# power_supplies.net
KiCad netlist of a schematic drawn in Altium Designer
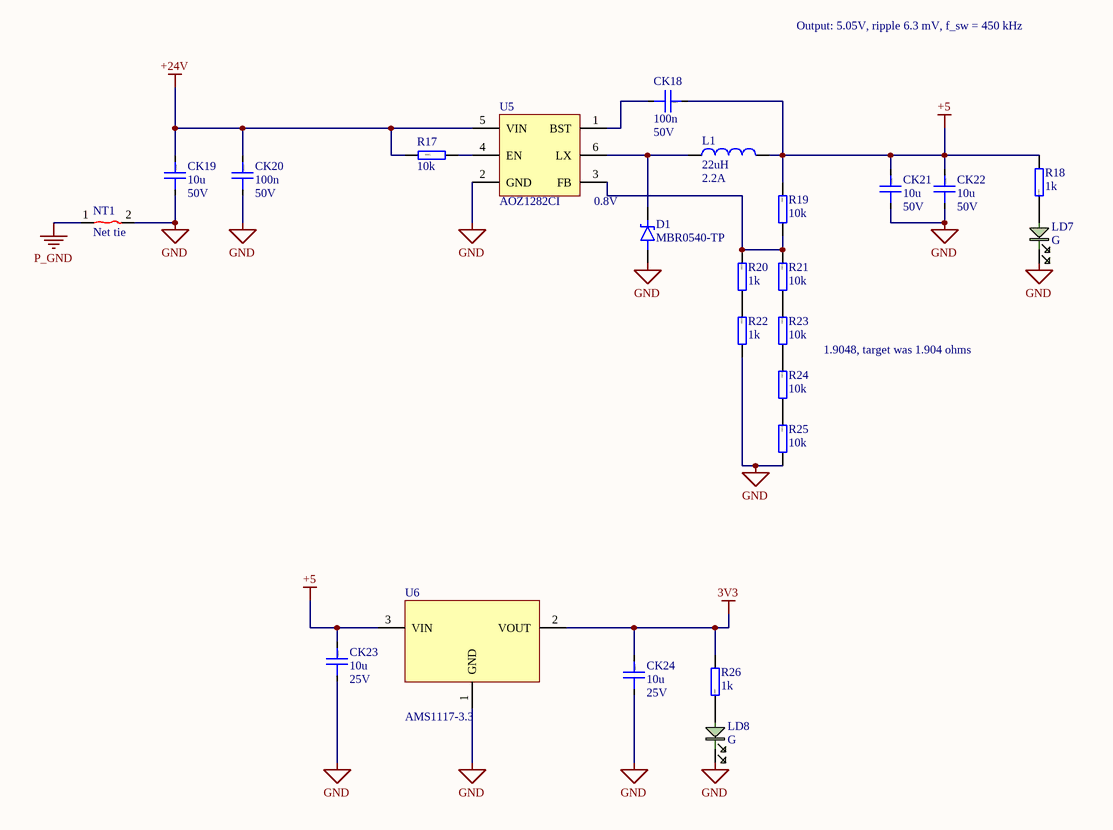
[diagram p0: power_supplies.SchDoc]

(export (version "E")
  (design (tool "Eeschema 10.0.6"))
  (components
    (comp (ref "CK18")
      (value "100n")
      (footprint "CAP0603")
      (description "50V 100nF X7R ±10% 0603 Multilayer Ceramic Capacitors MLCC - SMD/SMT ROHS")
      (fields (field (name "JLCPCB PART") "C14663") (field (name "VOLTAGE RATING") "50V"))
      (libsource (lib "Kubikova ultra knihovna") (part "Cap 100n 50V 0603"))
    )
    (comp (ref "CK19")
      (value "10u")
      (footprint "CAP1206")
      (description "50V 10uF X5R ±10% 1206 Multilayer Ceramic Capacitors MLCC - SMD/SMT ROHS")
      (fields (field (name "JLCPCB PART") "C13585") (field (name "VOLTAGE RATING") "50V"))
      (libsource (lib "Kubikova ultra knihovna") (part "Cap 10u 50V 1206"))
    )
    (comp (ref "CK20")
      (value "100n")
      (footprint "CAP0603")
      (description "50V 100nF X7R ±10% 0603 Multilayer Ceramic Capacitors MLCC - SMD/SMT ROHS")
      (fields (field (name "JLCPCB PART") "C14663") (field (name "VOLTAGE RATING") "50V"))
      (libsource (lib "Kubikova ultra knihovna") (part "Cap 100n 50V 0603"))
    )
    (comp (ref "CK21")
      (value "10u")
      (footprint "CAP1206")
      (description "50V 10uF X5R ±10% 1206 Multilayer Ceramic Capacitors MLCC - SMD/SMT ROHS")
      (fields (field (name "JLCPCB PART") "C13585") (field (name "VOLTAGE RATING") "50V"))
      (libsource (lib "Kubikova ultra knihovna") (part "Cap 10u 50V 1206"))
    )
    (comp (ref "CK22")
      (value "10u")
      (footprint "CAP1206")
      (description "50V 10uF X5R ±10% 1206 Multilayer Ceramic Capacitors MLCC - SMD/SMT ROHS")
      (fields (field (name "JLCPCB PART") "C13585") (field (name "VOLTAGE RATING") "50V"))
      (libsource (lib "Kubikova ultra knihovna") (part "Cap 10u 50V 1206"))
    )
    (comp (ref "CK23")
      (value "10u")
      (footprint "CAP0805")
      (description "25V 10uF X5R ±10% 0805 Multilayer Ceramic Capacitors MLCC - SMD/SMT ROHS")
      (fields (field (name "JLCPCB PART") "C15850") (field (name "VOLTAGE RATING") "25V"))
      (libsource (lib "Kubikova ultra knihovna") (part "Cap 10u 0805"))
    )
    (comp (ref "CK24")
      (value "10u")
      (footprint "CAP0805")
      (description "25V 10uF X5R ±10% 0805 Multilayer Ceramic Capacitors MLCC - SMD/SMT ROHS")
      (fields (field (name "JLCPCB PART") "C15850") (field (name "VOLTAGE RATING") "25V"))
      (libsource (lib "Kubikova ultra knihovna") (part "Cap 10u 0805"))
    )
    (comp (ref "D1")
      (value "MBR0540-TP")
      (footprint "Kubikova pcb knihovna:SOD3716X135N")
      (description "Diode 40 V 500mA Surface Mount SOD-123")
      (fields (field (name "MOUSER PART NUMBER") "833-MBR0540-TP") (field (name "JLCPCB PART") "C78744"))
      (libsource (lib "Kubikova ultra knihovna") (part "Diode Schottky MBR0540-TP"))
    )
    (comp (ref "L1")
      (value "22uH")
      (footprint "Kubikova pcb knihovna:ETQP3M_KVN")
      (description "2.2A 22uH Integrated molded inductor ±20% SMD,6.4x6mm Power Inductors ROHS")
      (fields
        (field (name "JLCPCB PART") "C412305")
        (field (name "TME PART") "ETQP3M220KVN")
        (field (name "CURRENT") "2.2A")
        (field (name "PUBLISHER") "Altium Limited")
      )
      (libsource (lib "Kubikova ultra knihovna") (part "Ind 22uH 2.2A"))
    )
    (comp (ref "LD7")
      (value "G")
      (footprint "0603_LED_G")
      (description "0603 Green Led")
      (fields (field (name "JLCPCB PART") "C22371297"))
      (libsource (lib "Kubikova ultra knihovna") (part "LED G 0603"))
    )
    (comp (ref "LD8")
      (value "G")
      (footprint "0603_LED_G")
      (description "0603 Green Led")
      (fields (field (name "JLCPCB PART") "C22371297"))
      (libsource (lib "Kubikova ultra knihovna") (part "LED G 0603"))
    )
    (comp (ref "NT1")
      (value "Net tie")
      (footprint "Net tie")
      (libsource (lib "Kubikova ultra knihovna") (part "Net tie"))
    )
    (comp (ref "R17")
      (value "10k")
      (footprint "RESC2012X06N(SMR0805)")
      (description "125mW Thick Film Resistors 150V ±100ppm/℃ ±1% 10kΩ 0805 Chip Resistor - Surface Mount ROHS")
      (fields (field (name "JLCPCB PART") "C17414"))
      (libsource (lib "Kubikova ultra knihovna") (part "Res 10k 0805"))
    )
    (comp (ref "R18")
      (value "1k")
      (footprint "RESC2012X06N(SMR0805)")
      (description "125mW Thick Film Resistors 150V ±100ppm/℃ ±1% 1kΩ 0805 Chip Resistor - Surface Mount ROHS")
      (fields (field (name "JLCPCB PART") "C17513") (field (name "AUTHOR") "JP/27.03.2014"))
      (libsource (lib "Kubikova ultra knihovna") (part "Res 1k 0805"))
    )
    (comp (ref "R19")
      (value "10k")
      (footprint "RESC2012X06N(SMR0805)")
      (description "125mW Thick Film Resistors 150V ±100ppm/℃ ±1% 10kΩ 0805 Chip Resistor - Surface Mount ROHS")
      (fields (field (name "JLCPCB PART") "C17414"))
      (libsource (lib "Kubikova ultra knihovna") (part "Res 10k 0805"))
    )
    (comp (ref "R20")
      (value "1k")
      (footprint "RESC2012X06N(SMR0805)")
      (description "125mW Thick Film Resistors 150V ±100ppm/℃ ±1% 1kΩ 0805 Chip Resistor - Surface Mount ROHS")
      (fields (field (name "JLCPCB PART") "C17513") (field (name "AUTHOR") "JP/27.03.2014"))
      (libsource (lib "Kubikova ultra knihovna") (part "Res 1k 0805"))
    )
    (comp (ref "R21")
      (value "10k")
      (footprint "RESC2012X06N(SMR0805)")
      (description "125mW Thick Film Resistors 150V ±100ppm/℃ ±1% 10kΩ 0805 Chip Resistor - Surface Mount ROHS")
      (fields (field (name "JLCPCB PART") "C17414"))
      (libsource (lib "Kubikova ultra knihovna") (part "Res 10k 0805"))
    )
    (comp (ref "R22")
      (value "1k")
      (footprint "RESC2012X06N(SMR0805)")
      (description "125mW Thick Film Resistors 150V ±100ppm/℃ ±1% 1kΩ 0805 Chip Resistor - Surface Mount ROHS")
      (fields (field (name "JLCPCB PART") "C17513") (field (name "AUTHOR") "JP/27.03.2014"))
      (libsource (lib "Kubikova ultra knihovna") (part "Res 1k 0805"))
    )
    (comp (ref "R23")
      (value "10k")
      (footprint "RESC2012X06N(SMR0805)")
      (description "125mW Thick Film Resistors 150V ±100ppm/℃ ±1% 10kΩ 0805 Chip Resistor - Surface Mount ROHS")
      (fields (field (name "JLCPCB PART") "C17414"))
      (libsource (lib "Kubikova ultra knihovna") (part "Res 10k 0805"))
    )
    (comp (ref "R24")
      (value "10k")
      (footprint "RESC2012X06N(SMR0805)")
      (description "125mW Thick Film Resistors 150V ±100ppm/℃ ±1% 10kΩ 0805 Chip Resistor - Surface Mount ROHS")
      (fields (field (name "JLCPCB PART") "C17414"))
      (libsource (lib "Kubikova ultra knihovna") (part "Res 10k 0805"))
    )
    (comp (ref "R25")
      (value "10k")
      (footprint "RESC2012X06N(SMR0805)")
      (description "125mW Thick Film Resistors 150V ±100ppm/℃ ±1% 10kΩ 0805 Chip Resistor - Surface Mount ROHS")
      (fields (field (name "JLCPCB PART") "C17414"))
      (libsource (lib "Kubikova ultra knihovna") (part "Res 10k 0805"))
    )
    (comp (ref "R26")
      (value "1k")
      (footprint "RESC2012X06N(SMR0805)")
      (description "125mW Thick Film Resistors 150V ±100ppm/℃ ±1% 1kΩ 0805 Chip Resistor - Surface Mount ROHS")
      (fields (field (name "JLCPCB PART") "C17513") (field (name "AUTHOR") "JP/27.03.2014"))
      (libsource (lib "Kubikova ultra knihovna") (part "Res 1k 0805"))
    )
    (comp (ref "U5")
      (value "AOZ1282CI")
      (footprint "Kubikova pcb knihovna:SOT23-6")
      (description "Step-down type Adjustable 800mV~36V 1.2A 4.5V~36V SOT-23-6 DC-DC Converters ROHS")
      (fields (field (name "JLCPCB PART") "C111916"))
      (libsource (lib "Kubikova ultra knihovna") (part "AOZ1282CI"))
    )
    (comp (ref "U6")
      (value "AMS1117-3.3")
      (footprint "SOT230P700X180-4M")
      (fields (field (name "JLCPCB PART") "C6186"))
      (libsource (lib "Kubikova ultra knihovna") (part "AMS1117-3.3"))
    )
  )
  (nets
    (net (code "1") (name "+5") (class "Default")
      (node (ref "CK18") (pin "1") (pinfunction "1_1") (pintype "passive"))
      (node (ref "CK21") (pin "1") (pinfunction "1_1") (pintype "passive"))
      (node (ref "CK22") (pin "1") (pinfunction "1_1") (pintype "passive"))
      (node (ref "CK23") (pin "1") (pinfunction "1_1") (pintype "passive"))
      (node (ref "L1") (pin "2") (pinfunction "2_2") (pintype "passive"))
      (node (ref "R18") (pin "1") (pinfunction "1_1") (pintype "passive"))
      (node (ref "R19") (pin "2") (pinfunction "2_2") (pintype "passive"))
      (node (ref "U6") (pin "3") (pinfunction "VIN_3") (pintype "power_in"))
    )
    (net (code "2") (name "+24V") (class "Default")
      (node (ref "CK19") (pin "1") (pinfunction "1_1") (pintype "passive"))
      (node (ref "CK20") (pin "1") (pinfunction "1_1") (pintype "passive"))
      (node (ref "R17") (pin "2") (pinfunction "2_2") (pintype "passive"))
      (node (ref "U5") (pin "5") (pinfunction "VIN_5") (pintype "passive"))
    )
    (net (code "3") (name "3V3") (class "Default")
      (node (ref "CK24") (pin "1") (pinfunction "1_1") (pintype "passive"))
      (node (ref "R26") (pin "1") (pinfunction "1_1") (pintype "passive"))
      (node (ref "U6") (pin "2") (pinfunction "VOUT_2") (pintype "power_in"))
    )
    (net (code "4") (name "GND") (class "Default")
      (node (ref "CK19") (pin "2") (pinfunction "2_2") (pintype "passive"))
      (node (ref "CK20") (pin "2") (pinfunction "2_2") (pintype "passive"))
      (node (ref "CK21") (pin "2") (pinfunction "2_2") (pintype "passive"))
      (node (ref "CK22") (pin "2") (pinfunction "2_2") (pintype "passive"))
      (node (ref "CK23") (pin "2") (pinfunction "2_2") (pintype "passive"))
      (node (ref "CK24") (pin "2") (pinfunction "2_2") (pintype "passive"))
      (node (ref "D1") (pin "2") (pinfunction "A_2") (pintype "passive"))
      (node (ref "LD7") (pin "2") (pintype "passive"))
      (node (ref "LD8") (pin "2") (pintype "passive"))
      (node (ref "NT1") (pin "2") (pinfunction "2_2") (pintype "passive"))
      (node (ref "R22") (pin "1") (pinfunction "1_1") (pintype "passive"))
      (node (ref "R25") (pin "1") (pinfunction "1_1") (pintype "passive"))
      (node (ref "U5") (pin "2") (pinfunction "GND_2") (pintype "passive"))
      (node (ref "U6") (pin "1") (pinfunction "GND_1") (pintype "power_in"))
    )
    (net (code "5") (name "Net-(D1-K)") (class "Default")
      (node (ref "D1") (pin "1") (pinfunction "K_1") (pintype "passive"))
      (node (ref "L1") (pin "1") (pinfunction "1_1") (pintype "passive"))
      (node (ref "U5") (pin "6") (pinfunction "LX_6") (pintype "passive"))
    )
    (net (code "6") (name "Net-(LD7-Pad1)") (class "Default")
      (node (ref "LD7") (pin "1") (pintype "passive"))
      (node (ref "R18") (pin "2") (pinfunction "2_2") (pintype "passive"))
    )
    (net (code "7") (name "Net-(LD8-Pad1)") (class "Default")
      (node (ref "LD8") (pin "1") (pintype "passive"))
      (node (ref "R26") (pin "2") (pinfunction "2_2") (pintype "passive"))
    )
    (net (code "8") (name "Net-(R20-Pad1)") (class "Default")
      (node (ref "R20") (pin "1") (pinfunction "1_1") (pintype "passive"))
      (node (ref "R22") (pin "2") (pinfunction "2_2") (pintype "passive"))
    )
    (net (code "9") (name "Net-(R21-Pad1)") (class "Default")
      (node (ref "R21") (pin "1") (pinfunction "1_1") (pintype "passive"))
      (node (ref "R23") (pin "2") (pinfunction "2_2") (pintype "passive"))
    )
    (net (code "10") (name "Net-(R23-Pad1)") (class "Default")
      (node (ref "R23") (pin "1") (pinfunction "1_1") (pintype "passive"))
      (node (ref "R24") (pin "2") (pinfunction "2_2") (pintype "passive"))
    )
    (net (code "11") (name "Net-(R24-Pad1)") (class "Default")
      (node (ref "R24") (pin "1") (pinfunction "1_1") (pintype "passive"))
      (node (ref "R25") (pin "2") (pinfunction "2_2") (pintype "passive"))
    )
    (net (code "12") (name "Net-(U5-BST)") (class "Default")
      (node (ref "CK18") (pin "2") (pinfunction "2_2") (pintype "passive"))
      (node (ref "U5") (pin "1") (pinfunction "BST_1") (pintype "passive"))
    )
    (net (code "13") (name "Net-(U5-EN)") (class "Default")
      (node (ref "R17") (pin "1") (pinfunction "1_1") (pintype "passive"))
      (node (ref "U5") (pin "4") (pinfunction "EN_4") (pintype "passive"))
    )
    (net (code "14") (name "Net-(U5-FB)") (class "Default")
      (node (ref "R19") (pin "1") (pinfunction "1_1") (pintype "passive"))
      (node (ref "R20") (pin "2") (pinfunction "2_2") (pintype "passive"))
      (node (ref "R21") (pin "2") (pinfunction "2_2") (pintype "passive"))
      (node (ref "U5") (pin "3") (pinfunction "FB_3") (pintype "passive"))
    )
    (net (code "15") (name "P_GND") (class "Default")
      (node (ref "NT1") (pin "1") (pinfunction "1_1") (pintype "passive"))
    )
  )
)
